# HV_Amp_Discrete.net
KiCad netlist of a schematic drawn in Altium Designer
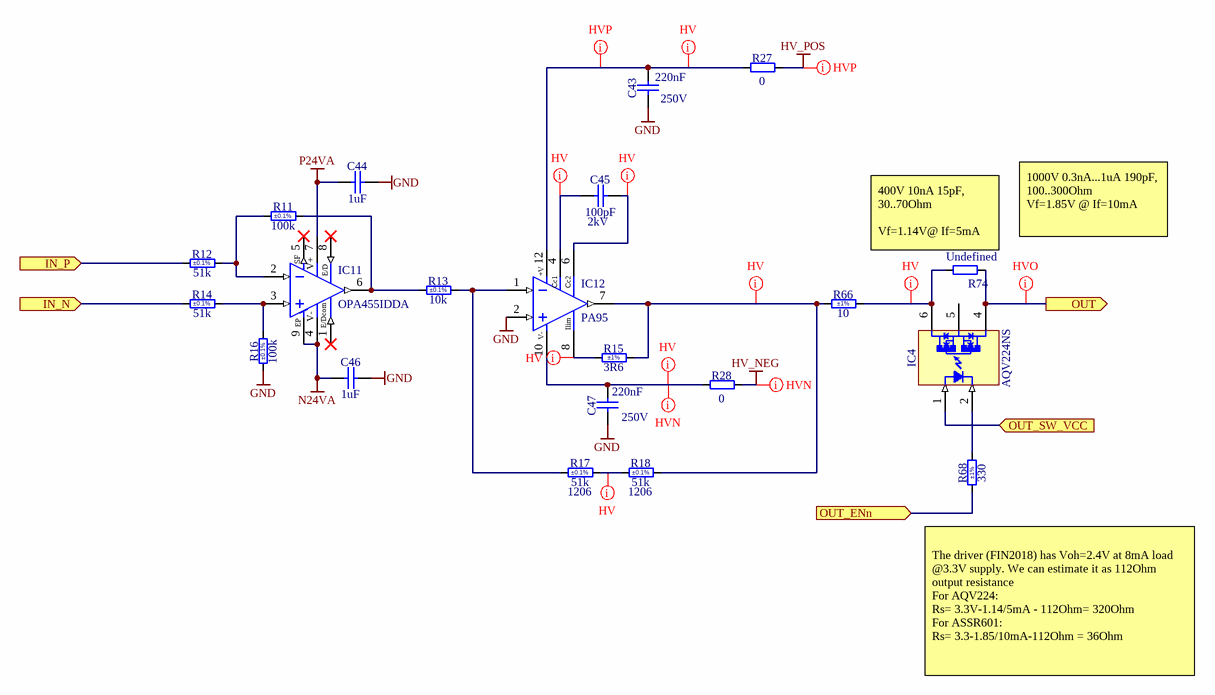
[diagram p0: HV_Amp_Discrete.SchDoc]

(export (version "E")
  (design (tool "Eeschema 10.0.6"))
  (components
    (comp (ref "C43")
      (value "220nF")
      (footprint "CAPC4532X165N")
      (description "Non-polarised capacitor")
      (fields
        (field (name "PART NUMBER") "CC1812_220NF_250V_10%_X7R_FT-CAP")
        (field (name "VOLTAGE") "250V")
        (field (name "TOLERANCE") "±10%")
        (field (name "AUTHOR") "CERN DEM JLC")
      )
      (libsource (lib "Capacitors") (part "Capacitor - non polarized"))
    )
    (comp (ref "C44")
      (value "1uF")
      (footprint "CAPC1608X87N")
      (description "Non-polarised capacitor")
      (fields
        (field (name "PART NUMBER") "CC0603_1UF_50V_10%_X5R")
        (field (name "VOLTAGE") "50V")
        (field (name "AUTHOR") "CERN DEM JMW")
      )
      (libsource (lib "Capacitors") (part "Capacitor - non polarized"))
    )
    (comp (ref "C45")
      (value "100pF")
      (footprint "CAPC4620X203N")
      (description "Non-polarised capacitor")
      (fields
        (field (name "PART NUMBER") "CC1808_100PF_2KV_5%_C0G")
        (field (name "VOLTAGE") "2kV")
        (field (name "TOLERANCE") "±5%")
        (field (name "AUTHOR") "CERN DEM JLC")
      )
      (libsource (lib "Capacitors") (part "Capacitor - non polarized"))
    )
    (comp (ref "C46")
      (value "1uF")
      (footprint "CAPC1608X87N")
      (description "Non-polarised capacitor")
      (fields
        (field (name "PART NUMBER") "CC0603_1UF_50V_10%_X5R")
        (field (name "VOLTAGE") "50V")
        (field (name "AUTHOR") "CERN DEM JMW")
      )
      (libsource (lib "Capacitors") (part "Capacitor - non polarized"))
    )
    (comp (ref "C47")
      (value "220nF")
      (footprint "CAPC4532X165N")
      (description "Non-polarised capacitor")
      (fields
        (field (name "PART NUMBER") "CC1812_220NF_250V_10%_X7R_FT-CAP")
        (field (name "VOLTAGE") "250V")
        (field (name "TOLERANCE") "±10%")
        (field (name "AUTHOR") "CERN DEM JLC")
      )
      (libsource (lib "Capacitors") (part "Capacitor - non polarized"))
    )
    (comp (ref "IC4")
      (value "AQV224NS")
      (footprint "PANASONIC_AQV22(SOP)")
      (description "PhotoMOS Relay 400V 40mA")
      (fields (field (name "MANUFACTURER") "PANASONIC") (field (name "AUTHOR") "GK"))
      (libsource (lib "Optoisolators") (part "OPTOMOS_AQV224NS"))
    )
    (comp (ref "IC11")
      (value "OPA455IDDA")
      (footprint "SOIC127P600X170-9N-R249X300")
      (description "High-Voltage (150V), High-Current (50mA) Operational Amplifier, G=1 Stable")
      (fields (field (name "MANUFACTURER") "TEXAS INSTRUMENTS") (field (name "AUTHOR") "GK"))
      (libsource (lib "ICs_Analog_Interfaces") (part "OA_OPA455"))
    )
    (comp (ref "IC12")
      (value "PA95")
      (footprint "APEX_PA95_hflip")
      (description "High Voltage Power Operational Amplifier")
      (fields
        (field (name "PART NUMBER") "PA95_hflip")
        (field (name "MANUFACTURER") "APEX")
        (field (name "AUTHOR") "GK")
      )
      (libsource (lib "ICs_Analog_Interfaces") (part "OA_PA95"))
    )
    (comp (ref "R11")
      (value "100k")
      (footprint "RESC1608X55N")
      (description "Resistor - 0.1%")
      (fields
        (field (name "TOLERANCE") "±0.1%")
        (field (name "PART NUMBER") "R0603_100K_0.1%_0.063W_10PPM")
        (field (name "POWER") "0.063W")
        (field (name "AUTHOR") "CERN DEM JLC")
      )
      (libsource (lib "Resistors") (part "Resistor - 0.1%"))
    )
    (comp (ref "R12")
      (value "51k")
      (footprint "RESC2012X60N")
      (description "Resistor - 0.1%")
      (fields
        (field (name "TOLERANCE") "±0.1%")
        (field (name "PART NUMBER") "R0805_51K_0.1%_0.125W_10PPM")
        (field (name "POWER") "0.125W")
        (field (name "AUTHOR") "CERN DEM BC")
      )
      (libsource (lib "Resistors") (part "Resistor - 0.1%"))
    )
    (comp (ref "R13")
      (value "10k")
      (footprint "RESC1608X64N")
      (description "Resistor - 0.1%")
      (fields
        (field (name "TOLERANCE") "±0.1%")
        (field (name "PART NUMBER") "R0603_10K_0.1%_0.1W_25PPM")
        (field (name "POWER") "0.1W")
        (field (name "AUTHOR") "CERN DEM JMW")
      )
      (libsource (lib "Resistors") (part "Resistor - 0.1%"))
    )
    (comp (ref "R14")
      (value "51k")
      (footprint "RESC2012X60N")
      (description "Resistor - 0.1%")
      (fields
        (field (name "TOLERANCE") "±0.1%")
        (field (name "PART NUMBER") "R0805_51K_0.1%_0.125W_10PPM")
        (field (name "POWER") "0.125W")
        (field (name "AUTHOR") "CERN DEM BC")
      )
      (libsource (lib "Resistors") (part "Resistor - 0.1%"))
    )
    (comp (ref "R15")
      (value "3R6")
      (footprint "RESC1608X55N")
      (description "Resistor - 1%")
      (fields
        (field (name "TOLERANCE") "±1%")
        (field (name "PART NUMBER") "R0603_3R6_1%_0.1W_200PPM")
        (field (name "POWER") "0.1W")
        (field (name "AUTHOR") "CERN DEM JLC")
      )
      (libsource (lib "Resistors") (part "Resistor - 1%"))
    )
    (comp (ref "R16")
      (value "100k")
      (footprint "RESC1608X55N")
      (description "Resistor - 0.1%")
      (fields
        (field (name "TOLERANCE") "±0.1%")
        (field (name "PART NUMBER") "R0603_100K_0.1%_0.063W_10PPM")
        (field (name "POWER") "0.063W")
        (field (name "AUTHOR") "CERN DEM JLC")
      )
      (libsource (lib "Resistors") (part "Resistor - 0.1%"))
    )
    (comp (ref "R17")
      (value "51k")
      (footprint "RESC3216X65N")
      (description "Resistor - 0.1%")
      (fields
        (field (name "TOLERANCE") "±0.1%")
        (field (name "PART NUMBER") "R1206_51K_0.1%_0.25W_25PPM")
        (field (name "POWER") "0.25W")
        (field (name "CASE") "1206")
        (field (name "AUTHOR") "CERN DEM JLC")
      )
      (libsource (lib "Resistors") (part "Resistor - 0.1%"))
    )
    (comp (ref "R18")
      (value "51k")
      (footprint "RESC3216X65N")
      (description "Resistor - 0.1%")
      (fields
        (field (name "TOLERANCE") "±0.1%")
        (field (name "PART NUMBER") "R1206_51K_0.1%_0.25W_25PPM")
        (field (name "POWER") "0.25W")
        (field (name "CASE") "1206")
        (field (name "AUTHOR") "CERN DEM JLC")
      )
      (libsource (lib "Resistors") (part "Resistor - 0.1%"))
    )
    (comp (ref "R27")
      (value "0")
      (footprint "RESC1608X55N")
      (description "Resistor")
      (fields
        (field (name "PART NUMBER") "R0603_0R_JUMPER")
        (field (name "MANUFACTURER") "GENERIC")
        (field (name "AUTHOR") "CERN DEM JLC")
      )
      (libsource (lib "Resistors") (part "Resistor"))
    )
    (comp (ref "R28")
      (value "0")
      (footprint "RESC1608X55N")
      (description "Resistor")
      (fields
        (field (name "PART NUMBER") "R0603_0R_JUMPER")
        (field (name "MANUFACTURER") "GENERIC")
        (field (name "AUTHOR") "CERN DEM JLC")
      )
      (libsource (lib "Resistors") (part "Resistor"))
    )
    (comp (ref "R66")
      (value "10")
      (footprint "RESC3216X65N")
      (description "Resistor - 1%")
      (fields
        (field (name "TOLERANCE") "±1%")
        (field (name "PART NUMBER") "R1206_10R_1%_0.25W_200PPM")
        (field (name "POWER") "0.25W")
        (field (name "AUTHOR") "CERN DEM JLC")
      )
      (libsource (lib "Resistors") (part "Resistor - 1%"))
    )
    (comp (ref "R68")
      (value "330")
      (footprint "RESC1005X40N")
      (description "Resistor - 1%")
      (fields
        (field (name "TOLERANCE") "±1%")
        (field (name "PART NUMBER") "R0402_330R_1%_0.0625W_100PPM")
        (field (name "POWER") "0.0625W")
        (field (name "AUTHOR") "CERN DEM JLC")
      )
      (libsource (lib "Resistors") (part "Resistor - 1%"))
    )
    (comp (ref "R74")
      (value "Undefined")
      (footprint "RESC3216X65N")
      (description "Resistor")
      (fields (field (name "PART NUMBER") "R1206_NO-VALUE") (field (name "AUTHOR") "CERN DEM JLC"))
      (libsource (lib "Resistors") (part "Resistor"))
    )
  )
  (nets
    (net (code "1") (name "/IN_N") (class "Default")
      (node (ref "R14") (pin "1") (pinfunction "1_1") (pintype "passive"))
    )
    (net (code "2") (name "/IN_P") (class "Default")
      (node (ref "R12") (pin "1") (pinfunction "1_1") (pintype "passive"))
    )
    (net (code "3") (name "/OUT") (class "Default")
      (node (ref "IC4") (pin "4") (pinfunction "4_4") (pintype "passive"))
      (node (ref "R74") (pin "2") (pinfunction "2_2") (pintype "passive"))
    )
    (net (code "4") (name "/OUT_ENn") (class "Default")
      (node (ref "R68") (pin "1") (pinfunction "1_1") (pintype "passive"))
    )
    (net (code "5") (name "/OUT_SW_VCC") (class "Default")
      (node (ref "IC4") (pin "1") (pinfunction "A_1") (pintype "input"))
    )
    (net (code "6") (name "GND") (class "Default")
      (node (ref "C43") (pin "1") (pinfunction "1_1") (pintype "passive"))
      (node (ref "C44") (pin "2") (pinfunction "2_2") (pintype "passive"))
      (node (ref "C46") (pin "2") (pinfunction "2_2") (pintype "passive"))
      (node (ref "C47") (pin "1") (pinfunction "1_1") (pintype "passive"))
      (node (ref "IC12") (pin "2") (pinfunction "IN+_2") (pintype "input"))
      (node (ref "R16") (pin "1") (pinfunction "1_1") (pintype "passive"))
    )
    (net (code "7") (name "HV_NEG") (class "Default")
      (node (ref "R28") (pin "2") (pinfunction "2_2") (pintype "passive"))
    )
    (net (code "8") (name "HV_POS") (class "Default")
      (node (ref "R27") (pin "2") (pinfunction "2_2") (pintype "passive"))
    )
    (net (code "9") (name "N24VA") (class "Default")
      (node (ref "C46") (pin "1") (pinfunction "1_1") (pintype "passive"))
      (node (ref "IC11") (pin "4") (pinfunction "V-_4") (pintype "power_in"))
      (node (ref "IC11") (pin "9") (pinfunction "Exposed_Pad_9") (pintype "power_in"))
    )
    (net (code "10") (name "Net-(IC4-K)") (class "Default")
      (node (ref "IC4") (pin "2") (pinfunction "K_2") (pintype "input"))
      (node (ref "R68") (pin "2") (pinfunction "2_2") (pintype "passive"))
    )
    (net (code "11") (name "Net-(IC4-Pad6)") (class "Default")
      (node (ref "IC4") (pin "6") (pinfunction "6_6") (pintype "passive"))
      (node (ref "R66") (pin "2") (pinfunction "2_2") (pintype "passive"))
      (node (ref "R74") (pin "1") (pinfunction "1_1") (pintype "passive"))
    )
    (net (code "12") (name "Net-(IC11-IN+)") (class "Default")
      (node (ref "IC11") (pin "3") (pinfunction "IN+_3") (pintype "input"))
      (node (ref "R14") (pin "2") (pinfunction "2_2") (pintype "passive"))
      (node (ref "R16") (pin "2") (pinfunction "2_2") (pintype "passive"))
    )
    (net (code "13") (name "Net-(IC11-IN-)") (class "Default")
      (node (ref "IC11") (pin "2") (pinfunction "IN-_2") (pintype "input"))
      (node (ref "R11") (pin "1") (pinfunction "1_1") (pintype "passive"))
      (node (ref "R12") (pin "2") (pinfunction "2_2") (pintype "passive"))
    )
    (net (code "14") (name "Net-(IC11-OUT)") (class "Default")
      (node (ref "IC11") (pin "6") (pinfunction "OUT_6") (pintype "output"))
      (node (ref "R11") (pin "2") (pinfunction "2_2") (pintype "passive"))
      (node (ref "R13") (pin "1") (pinfunction "1_1") (pintype "passive"))
    )
    (net (code "15") (name "Net-(IC12-+Vs)") (class "Default")
      (node (ref "C43") (pin "2") (pinfunction "2_2") (pintype "passive"))
      (node (ref "IC12") (pin "12") (pinfunction "+Vs_12") (pintype "power_in"))
      (node (ref "R27") (pin "1") (pinfunction "1_1") (pintype "passive"))
    )
    (net (code "16") (name "Net-(IC12--Vs)") (class "Default")
      (node (ref "C47") (pin "2") (pinfunction "2_2") (pintype "passive"))
      (node (ref "IC12") (pin "10") (pinfunction "-Vs_10") (pintype "power_in"))
      (node (ref "R28") (pin "1") (pinfunction "1_1") (pintype "passive"))
    )
    (net (code "17") (name "Net-(IC12-Cc1)") (class "Default")
      (node (ref "C45") (pin "1") (pinfunction "1_1") (pintype "passive"))
      (node (ref "IC12") (pin "4") (pinfunction "Cc1_4") (pintype "passive"))
    )
    (net (code "18") (name "Net-(IC12-Cc2)") (class "Default")
      (node (ref "C45") (pin "2") (pinfunction "2_2") (pintype "passive"))
      (node (ref "IC12") (pin "6") (pinfunction "Cc2_6") (pintype "passive"))
    )
    (net (code "19") (name "Net-(IC12-ILIM)") (class "Default")
      (node (ref "IC12") (pin "8") (pinfunction "ILIM_8") (pintype "passive"))
      (node (ref "R15") (pin "1") (pinfunction "1_1") (pintype "passive"))
    )
    (net (code "20") (name "Net-(IC12-IN-)") (class "Default")
      (node (ref "IC12") (pin "1") (pinfunction "IN-_1") (pintype "input"))
      (node (ref "R13") (pin "2") (pinfunction "2_2") (pintype "passive"))
      (node (ref "R17") (pin "1") (pinfunction "1_1") (pintype "passive"))
    )
    (net (code "21") (name "Net-(IC12-OUT)") (class "Default")
      (node (ref "IC12") (pin "7") (pinfunction "OUT_7") (pintype "output"))
      (node (ref "R15") (pin "2") (pinfunction "2_2") (pintype "passive"))
      (node (ref "R18") (pin "2") (pinfunction "2_2") (pintype "passive"))
      (node (ref "R66") (pin "1") (pinfunction "1_1") (pintype "passive"))
    )
    (net (code "22") (name "Net-(R17-Pad2)") (class "Default")
      (node (ref "R17") (pin "2") (pinfunction "2_2") (pintype "passive"))
      (node (ref "R18") (pin "1") (pinfunction "1_1") (pintype "passive"))
    )
    (net (code "23") (name "P24VA") (class "Default")
      (node (ref "C44") (pin "1") (pinfunction "1_1") (pintype "passive"))
      (node (ref "IC11") (pin "7") (pinfunction "V+_7") (pintype "power_in"))
    )
    (net (code "24") (name "unconnected-(IC4-Pad5)") (class "Default")
      (node (ref "IC4") (pin "5") (pinfunction "5_5") (pintype "passive"))
    )
    (net (code "25") (name "unconnected-(IC11-E{slash}B-Pad8)") (class "Default")
      (node (ref "IC11") (pin "8") (pinfunction "E/B_8") (pintype "input+no_connect"))
    )
    (net (code "26") (name "unconnected-(IC11-E{slash}Dcommon-Pad1)") (class "Default")
      (node (ref "IC11") (pin "1") (pinfunction "E/Dcommon_1") (pintype "input+no_connect"))
    )
    (net (code "27") (name "unconnected-(IC11-Status_Flag-Pad5)") (class "Default")
      (node (ref "IC11") (pin "5") (pinfunction "Status_Flag_5") (pintype "output+no_connect"))
    )
  )
)
